# Sch_SD.net
KiCad netlist of a schematic drawn in Altium Designer
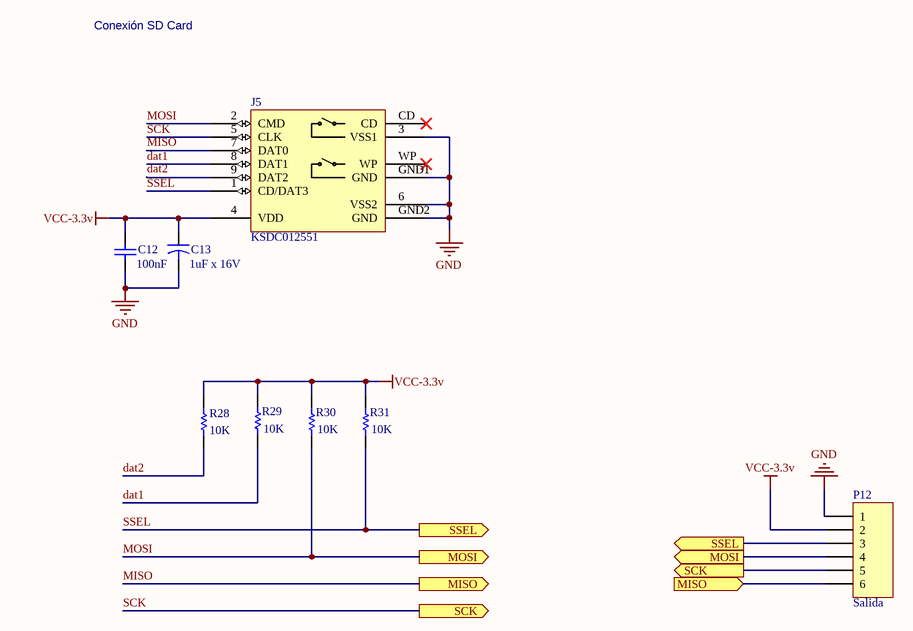
[diagram p0: Sch_SD.SchDoc]

(export (version "E")
  (design (tool "Eeschema 10.0.6"))
  (components
    (comp (ref "C12")
      (value "100nF")
      (footprint "RAD-0.3")
      (description "Capacitor")
      (fields (field (name "Comment") "Cap") (field (name "PUBLISHER") "Altium Limited"))
      (libsource (lib "Miscellaneous Devices") (part "Cap"))
    )
    (comp (ref "C13")
      (value "1uF x 16V")
      (footprint "CAPR5-4X5")
      (description "Capacitor")
      (fields (field (name "Comment") "Cap2") (field (name "PUBLISHER") "Altium Limited"))
      (libsource (lib "Miscellaneous Devices") (part "Cap2"))
    )
    (comp (ref "J5")
      (value "KSDC012551")
      (footprint "KONV-KSDC012551_V")
      (description "Secure Digital Card Socket")
      (fields (field (name "MANUFACTURER") "Konvee Electronic"))
      (libsource (lib "Altium Content Vault") (part "KONV-KSDC012551"))
    )
    (comp (ref "P12")
      (value "Salida")
      (footprint "HDR1X6")
      (description "Header, 6-Pin")
      (fields (field (name "PUBLISHER") "Altium Limited"))
      (libsource (lib "Miscellaneous Connectors") (part "Header 6"))
    )
    (comp (ref "R28")
      (value "10K")
      (footprint "AXIAL-0.3")
      (description "Resistor")
      (fields (field (name "Comment") "Res1") (field (name "PUBLISHER") "Altium Limited"))
      (libsource (lib "Miscellaneous Devices") (part "Res1"))
    )
    (comp (ref "R29")
      (value "10K")
      (footprint "AXIAL-0.3")
      (description "Resistor")
      (fields (field (name "Comment") "Res1") (field (name "PUBLISHER") "Altium Limited"))
      (libsource (lib "Miscellaneous Devices") (part "Res1"))
    )
    (comp (ref "R30")
      (value "10K")
      (footprint "AXIAL-0.3")
      (description "Resistor")
      (fields (field (name "Comment") "Res1") (field (name "PUBLISHER") "Altium Limited"))
      (libsource (lib "Miscellaneous Devices") (part "Res1"))
    )
    (comp (ref "R31")
      (value "10K")
      (footprint "AXIAL-0.3")
      (description "Resistor")
      (fields (field (name "Comment") "Res1") (field (name "PUBLISHER") "Altium Limited"))
      (libsource (lib "Miscellaneous Devices") (part "Res1"))
    )
  )
  (nets
    (net (code "1") (name "/MISO") (class "Default")
      (node (ref "J5") (pin "7") (pinfunction "DAT0_7") (pintype "bidirectional"))
      (node (ref "P12") (pin "6") (pinfunction "6_6") (pintype "passive"))
    )
    (net (code "2") (name "/MOSI") (class "Default")
      (node (ref "J5") (pin "2") (pinfunction "CMD_2") (pintype "bidirectional"))
      (node (ref "P12") (pin "4") (pinfunction "4_4") (pintype "passive"))
      (node (ref "R30") (pin "1") (pinfunction "1_1") (pintype "passive"))
    )
    (net (code "3") (name "/SCK") (class "Default")
      (node (ref "J5") (pin "5") (pinfunction "CLK_5") (pintype "bidirectional"))
      (node (ref "P12") (pin "5") (pinfunction "5_5") (pintype "passive"))
    )
    (net (code "4") (name "/SSEL") (class "Default")
      (node (ref "J5") (pin "1") (pinfunction "CD/DAT3_1") (pintype "bidirectional"))
      (node (ref "P12") (pin "3") (pinfunction "3_3") (pintype "passive"))
      (node (ref "R31") (pin "1") (pinfunction "1_1") (pintype "passive"))
    )
    (net (code "5") (name "/dat1") (class "Default")
      (node (ref "J5") (pin "8") (pinfunction "DAT1_8") (pintype "bidirectional"))
      (node (ref "R29") (pin "1") (pinfunction "1_1") (pintype "passive"))
    )
    (net (code "6") (name "/dat2") (class "Default")
      (node (ref "J5") (pin "9") (pinfunction "DAT2_9") (pintype "bidirectional"))
      (node (ref "R28") (pin "1") (pinfunction "1_1") (pintype "passive"))
    )
    (net (code "7") (name "GND") (class "Default")
      (node (ref "C12") (pin "1") (pinfunction "1_1") (pintype "passive"))
      (node (ref "C13") (pin "2") (pinfunction "2_2") (pintype "passive"))
      (node (ref "J5") (pin "3") (pinfunction "VSS1_3") (pintype "power_in"))
      (node (ref "J5") (pin "6") (pinfunction "VSS2_6") (pintype "power_in"))
      (node (ref "J5") (pin "GND1") (pinfunction "GND_GND1") (pintype "power_in"))
      (node (ref "J5") (pin "GND2") (pinfunction "GND_GND2") (pintype "power_in"))
      (node (ref "P12") (pin "1") (pinfunction "1_1") (pintype "passive"))
    )
    (net (code "8") (name "VCC-3.3v") (class "Default")
      (node (ref "C12") (pin "2") (pinfunction "2_2") (pintype "passive"))
      (node (ref "C13") (pin "1") (pinfunction "1_1") (pintype "passive"))
      (node (ref "J5") (pin "4") (pinfunction "VDD_4") (pintype "power_in"))
      (node (ref "P12") (pin "2") (pinfunction "2_2") (pintype "passive"))
      (node (ref "R28") (pin "2") (pinfunction "2_2") (pintype "passive"))
      (node (ref "R29") (pin "2") (pinfunction "2_2") (pintype "passive"))
      (node (ref "R30") (pin "2") (pinfunction "2_2") (pintype "passive"))
      (node (ref "R31") (pin "2") (pinfunction "2_2") (pintype "passive"))
    )
    (net (code "9") (name "unconnected-(J5-PadCD)") (class "Default")
      (node (ref "J5") (pin "CD") (pinfunction "CD_CD") (pintype "open_collector+no_connect"))
    )
    (net (code "10") (name "unconnected-(J5-PadWP)") (class "Default")
      (node (ref "J5") (pin "WP") (pinfunction "WP_WP") (pintype "open_collector+no_connect"))
    )
  )
)
